# Power_MPU.net
KiCad netlist of a schematic drawn in Altium Designer
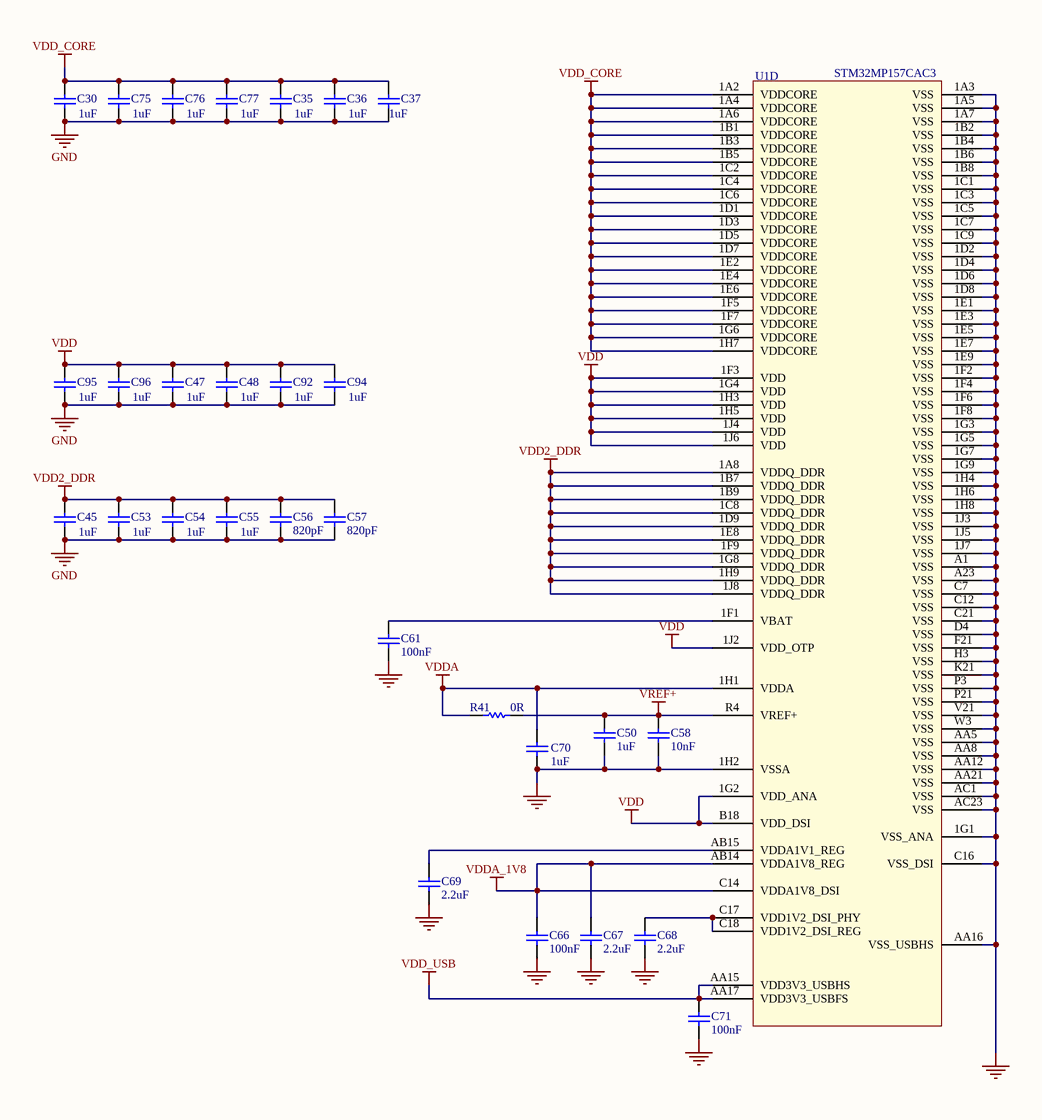
[diagram p0: Power_MPU.SchDoc]

(export (version "E")
  (design (tool "Eeschema 10.0.6"))
  (components
    (comp (ref "C30")
      (value "1uF")
      (footprint "C0402")
      (description "Capacitor, MLCC, 1uF, 25V, X5R, 10%, 0402, T=0,5mm")
      (fields
        (field (name "INTERNAL_PART_NUMBER") "MCD-00095")
        (field (name "MANUFACTURER_PART_NUMBER") "GRM155R61E105KA12")
        (field (name "PROVIDED_BY") "SUBCO")
      )
      (libsource (lib "MCD_PARTS_database") (part "Capacitor"))
    )
    (comp (ref "C35")
      (value "1uF")
      (footprint "C0402")
      (description "Capacitor, MLCC, 1uF, 25V, X5R, 10%, 0402, T=0,5mm")
      (fields
        (field (name "INTERNAL_PART_NUMBER") "MCD-00095")
        (field (name "MANUFACTURER_PART_NUMBER") "GRM155R61E105KA12")
        (field (name "PROVIDED_BY") "SUBCO")
      )
      (libsource (lib "MCD_PARTS_database") (part "Capacitor"))
    )
    (comp (ref "C36")
      (value "1uF")
      (footprint "C0402")
      (description "Capacitor, MLCC, 1uF, 25V, X5R, 10%, 0402, T=0,5mm")
      (fields
        (field (name "INTERNAL_PART_NUMBER") "MCD-00095")
        (field (name "MANUFACTURER_PART_NUMBER") "GRM155R61E105KA12")
        (field (name "PROVIDED_BY") "SUBCO")
      )
      (libsource (lib "MCD_PARTS_database") (part "Capacitor"))
    )
    (comp (ref "C37")
      (value "1uF")
      (footprint "C0402")
      (description "Capacitor, MLCC, 1uF, 25V, X5R, 10%, 0402, T=0,5mm")
      (fields
        (field (name "INTERNAL_PART_NUMBER") "MCD-00095")
        (field (name "MANUFACTURER_PART_NUMBER") "GRM155R61E105KA12")
        (field (name "PROVIDED_BY") "SUBCO")
      )
      (libsource (lib "MCD_PARTS_database") (part "Capacitor"))
    )
    (comp (ref "C45")
      (value "1uF")
      (footprint "C0402")
      (description "Capacitor, MLCC, 1uF, 25V, X5R, 10%, 0402, T=0,5mm")
      (fields
        (field (name "INTERNAL_PART_NUMBER") "MCD-00095")
        (field (name "MANUFACTURER_PART_NUMBER") "GRM155R61E105KA12")
        (field (name "PROVIDED_BY") "SUBCO")
      )
      (libsource (lib "MCD_PARTS_database") (part "Capacitor"))
    )
    (comp (ref "C47")
      (value "1uF")
      (footprint "C0402")
      (description "Capacitor, MLCC, 1uF, 25V, X5R, 10%, 0402, T=0,5mm")
      (fields
        (field (name "INTERNAL_PART_NUMBER") "MCD-00095")
        (field (name "MANUFACTURER_PART_NUMBER") "GRM155R61E105KA12")
        (field (name "PROVIDED_BY") "SUBCO")
      )
      (libsource (lib "MCD_PARTS_database") (part "Capacitor"))
    )
    (comp (ref "C48")
      (value "1uF")
      (footprint "C0402")
      (description "Capacitor, MLCC, 1uF, 25V, X5R, 10%, 0402, T=0,5mm")
      (fields
        (field (name "INTERNAL_PART_NUMBER") "MCD-00095")
        (field (name "MANUFACTURER_PART_NUMBER") "GRM155R61E105KA12")
        (field (name "PROVIDED_BY") "SUBCO")
      )
      (libsource (lib "MCD_PARTS_database") (part "Capacitor"))
    )
    (comp (ref "C50")
      (value "1uF")
      (footprint "C0402")
      (description "Capacitor, MLCC, 1uF, 25V, X5R, 10%, 0402, T=0,5mm")
      (fields
        (field (name "INTERNAL_PART_NUMBER") "MCD-00095")
        (field (name "MANUFACTURER_PART_NUMBER") "GRM155R61E105KA12")
        (field (name "PROVIDED_BY") "SUBCO")
      )
      (libsource (lib "MCD_PARTS_database") (part "Capacitor"))
    )
    (comp (ref "C53")
      (value "1uF")
      (footprint "C0402")
      (description "Capacitor, MLCC, 1uF, 25V, X5R, 10%, 0402, T=0,5mm")
      (fields
        (field (name "INTERNAL_PART_NUMBER") "MCD-00095")
        (field (name "MANUFACTURER_PART_NUMBER") "GRM155R61E105KA12")
        (field (name "PROVIDED_BY") "SUBCO")
      )
      (libsource (lib "MCD_PARTS_database") (part "Capacitor"))
    )
    (comp (ref "C54")
      (value "1uF")
      (footprint "C0402")
      (description "Capacitor, MLCC, 1uF, 25V, X5R, 10%, 0402, T=0,5mm")
      (fields
        (field (name "INTERNAL_PART_NUMBER") "MCD-00095")
        (field (name "MANUFACTURER_PART_NUMBER") "GRM155R61E105KA12")
        (field (name "PROVIDED_BY") "SUBCO")
      )
      (libsource (lib "MCD_PARTS_database") (part "Capacitor"))
    )
    (comp (ref "C55")
      (value "1uF")
      (footprint "C0402")
      (description "Capacitor, MLCC, 1uF, 25V, X5R, 10%, 0402, T=0,5mm")
      (fields
        (field (name "INTERNAL_PART_NUMBER") "MCD-00095")
        (field (name "MANUFACTURER_PART_NUMBER") "GRM155R61E105KA12")
        (field (name "PROVIDED_BY") "SUBCO")
      )
      (libsource (lib "MCD_PARTS_database") (part "Capacitor"))
    )
    (comp (ref "C56")
      (value "820pF")
      (footprint "C0402")
      (description "Capacitor, MLCC, 820pF, 50V, X7R, 10%, 0402, T=0.55mm")
      (fields
        (field (name "INTERNAL_PART_NUMBER") "MCD-01508")
        (field (name "MANUFACTURER_PART_NUMBER") "CC0402KRX7R9BB821")
        (field (name "PROVIDED_BY") "SUBCO")
      )
      (libsource (lib "MCD_PARTS_database") (part "Capacitor"))
    )
    (comp (ref "C57")
      (value "820pF")
      (footprint "C0402")
      (description "Capacitor, MLCC, 820pF, 50V, X7R, 10%, 0402, T=0.55mm")
      (fields
        (field (name "INTERNAL_PART_NUMBER") "MCD-01508")
        (field (name "MANUFACTURER_PART_NUMBER") "CC0402KRX7R9BB821")
        (field (name "PROVIDED_BY") "SUBCO")
      )
      (libsource (lib "MCD_PARTS_database") (part "Capacitor"))
    )
    (comp (ref "C58")
      (value "10nF")
      (footprint "C0402")
      (description "Capacitor, MLCC, 10nF, 16V, X7R, 10%, 0402, T=0.5mm")
      (fields
        (field (name "INTERNAL_PART_NUMBER") "MCD-00011")
        (field (name "MANUFACTURER_PART_NUMBER") "CC0402KRX7R7BB103")
        (field (name "PROVIDED_BY") "SUBCO")
      )
      (libsource (lib "MCD_PARTS_database") (part "Capacitor"))
    )
    (comp (ref "C61")
      (value "100nF")
      (footprint "C0402")
      (description "Capacitor, MLCC, 100nF, 16V, X7R, 10%, 0402, T=0.5mm")
      (fields
        (field (name "INTERNAL_PART_NUMBER") "MCD-00006")
        (field (name "MANUFACTURER_PART_NUMBER") "CC0402KRX7R7BB104")
        (field (name "PROVIDED_BY") "SUBCO")
      )
      (libsource (lib "MCD_PARTS_database") (part "Capacitor"))
    )
    (comp (ref "C66")
      (value "100nF")
      (footprint "C0402")
      (description "Capacitor, MLCC, 100nF, 16V, X7R, 10%, 0402, T=0.5mm")
      (fields
        (field (name "INTERNAL_PART_NUMBER") "MCD-00006")
        (field (name "MANUFACTURER_PART_NUMBER") "CC0402KRX7R7BB104")
        (field (name "PROVIDED_BY") "SUBCO")
      )
      (libsource (lib "MCD_PARTS_database") (part "Capacitor"))
    )
    (comp (ref "C67")
      (value "2.2uF")
      (footprint "C0402")
      (description "Capacitor,MLCC,2.2uF,6V3,X5R,10%,0402,T=0.5")
      (fields
        (field (name "INTERNAL_PART_NUMBER") "MCD-01823")
        (field (name "MANUFACTURER_PART_NUMBER") "GRM155R60J225KE95D")
        (field (name "PROVIDED_BY") "SUBCO")
      )
      (libsource (lib "MCD_PARTS_database") (part "Capacitor"))
    )
    (comp (ref "C68")
      (value "2.2uF")
      (footprint "C0402")
      (description "Capacitor,MLCC,2.2uF,6V3,X5R,10%,0402,T=0.5")
      (fields
        (field (name "INTERNAL_PART_NUMBER") "MCD-01823")
        (field (name "MANUFACTURER_PART_NUMBER") "GRM155R60J225KE95D")
        (field (name "PROVIDED_BY") "SUBCO")
      )
      (libsource (lib "MCD_PARTS_database") (part "Capacitor"))
    )
    (comp (ref "C69")
      (value "2.2uF")
      (footprint "C0402")
      (description "Capacitor,MLCC,2.2uF,6V3,X5R,10%,0402,T=0.5")
      (fields
        (field (name "INTERNAL_PART_NUMBER") "MCD-01823")
        (field (name "MANUFACTURER_PART_NUMBER") "GRM155R60J225KE95D")
        (field (name "PROVIDED_BY") "SUBCO")
      )
      (libsource (lib "MCD_PARTS_database") (part "Capacitor"))
    )
    (comp (ref "C70")
      (value "1uF")
      (footprint "C0402")
      (description "Capacitor, MLCC, 1uF, 25V, X5R, 10%, 0402, T=0,5mm")
      (fields
        (field (name "INTERNAL_PART_NUMBER") "MCD-00095")
        (field (name "MANUFACTURER_PART_NUMBER") "GRM155R61E105KA12")
        (field (name "PROVIDED_BY") "SUBCO")
      )
      (libsource (lib "MCD_PARTS_database") (part "Capacitor"))
    )
    (comp (ref "C71")
      (value "100nF")
      (footprint "C0402")
      (description "Capacitor, MLCC, 100nF, 16V, X7R, 10%, 0402, T=0.5mm")
      (fields
        (field (name "INTERNAL_PART_NUMBER") "MCD-00006")
        (field (name "MANUFACTURER_PART_NUMBER") "CC0402KRX7R7BB104")
        (field (name "PROVIDED_BY") "SUBCO")
      )
      (libsource (lib "MCD_PARTS_database") (part "Capacitor"))
    )
    (comp (ref "C75")
      (value "1uF")
      (footprint "C0402")
      (description "Capacitor, MLCC, 1uF, 25V, X5R, 10%, 0402, T=0,5mm")
      (fields
        (field (name "INTERNAL_PART_NUMBER") "MCD-00095")
        (field (name "MANUFACTURER_PART_NUMBER") "GRM155R61E105KA12")
        (field (name "PROVIDED_BY") "SUBCO")
      )
      (libsource (lib "MCD_PARTS_database") (part "Capacitor"))
    )
    (comp (ref "C76")
      (value "1uF")
      (footprint "C0402")
      (description "Capacitor, MLCC, 1uF, 25V, X5R, 10%, 0402, T=0,5mm")
      (fields
        (field (name "INTERNAL_PART_NUMBER") "MCD-00095")
        (field (name "MANUFACTURER_PART_NUMBER") "GRM155R61E105KA12")
        (field (name "PROVIDED_BY") "SUBCO")
      )
      (libsource (lib "MCD_PARTS_database") (part "Capacitor"))
    )
    (comp (ref "C77")
      (value "1uF")
      (footprint "C0402")
      (description "Capacitor, MLCC, 1uF, 25V, X5R, 10%, 0402, T=0,5mm")
      (fields
        (field (name "INTERNAL_PART_NUMBER") "MCD-00095")
        (field (name "MANUFACTURER_PART_NUMBER") "GRM155R61E105KA12")
        (field (name "PROVIDED_BY") "SUBCO")
      )
      (libsource (lib "MCD_PARTS_database") (part "Capacitor"))
    )
    (comp (ref "C92")
      (value "1uF")
      (footprint "C0402")
      (description "Capacitor, MLCC, 1uF, 25V, X5R, 10%, 0402, T=0,5mm")
      (fields
        (field (name "INTERNAL_PART_NUMBER") "MCD-00095")
        (field (name "MANUFACTURER_PART_NUMBER") "GRM155R61E105KA12")
        (field (name "PROVIDED_BY") "SUBCO")
      )
      (libsource (lib "MCD_PARTS_database") (part "Capacitor"))
    )
    (comp (ref "C94")
      (value "1uF")
      (footprint "C0402")
      (description "Capacitor, MLCC, 1uF, 25V, X5R, 10%, 0402, T=0,5mm")
      (fields
        (field (name "INTERNAL_PART_NUMBER") "MCD-00095")
        (field (name "MANUFACTURER_PART_NUMBER") "GRM155R61E105KA12")
        (field (name "PROVIDED_BY") "SUBCO")
      )
      (libsource (lib "MCD_PARTS_database") (part "Capacitor"))
    )
    (comp (ref "C95")
      (value "1uF")
      (footprint "C0402")
      (description "Capacitor, MLCC, 1uF, 25V, X5R, 10%, 0402, T=0,5mm")
      (fields
        (field (name "INTERNAL_PART_NUMBER") "MCD-00095")
        (field (name "MANUFACTURER_PART_NUMBER") "GRM155R61E105KA12")
        (field (name "PROVIDED_BY") "SUBCO")
      )
      (libsource (lib "MCD_PARTS_database") (part "Capacitor"))
    )
    (comp (ref "C96")
      (value "1uF")
      (footprint "C0402")
      (description "Capacitor, MLCC, 1uF, 25V, X5R, 10%, 0402, T=0,5mm")
      (fields
        (field (name "INTERNAL_PART_NUMBER") "MCD-00095")
        (field (name "MANUFACTURER_PART_NUMBER") "GRM155R61E105KA12")
        (field (name "PROVIDED_BY") "SUBCO")
      )
      (libsource (lib "MCD_PARTS_database") (part "Capacitor"))
    )
    (comp (ref "R41")
      (value "0R")
      (footprint "R0402")
      (description "Resistor,0R,0402,5%,1/16W")
      (fields
        (field (name "INTERNAL_PART_NUMBER") "MCD-00052")
        (field (name "MANUFACTURER_PART_NUMBER") "RC0402JR-070RL")
        (field (name "PROVIDED_BY") "SUBCO")
      )
      (libsource (lib "MCD_PARTS_database") (part "Resistor"))
    )
    (comp (ref "U1")
      (value "STM32MP157CAC3")
      (footprint "ICC_TFBGA361_12X12_STM32MP157CAC3_P050-065")
      (description "MPU TFBGA12x12 secure boot+crypto")
      (fields
        (field (name "INTERNAL_PART_NUMBER") "MCD-00677")
        (field (name "MANUFACTURER") "STMICROELECTRONICS")
        (field (name "PROVIDED_BY") "SUBCO with ST control")
      )
      (libsource (lib "MCD_PARTS_database") (part "STM32MP157CAC3"))
    )
  )
  (nets
    (net (code "1") (name "GND") (class "Default")
      (node (ref "C30") (pin "1") (pinfunction "1_1") (pintype "passive"))
      (node (ref "C35") (pin "1") (pinfunction "1_1") (pintype "passive"))
      (node (ref "C36") (pin "1") (pinfunction "1_1") (pintype "passive"))
      (node (ref "C37") (pin "1") (pinfunction "1_1") (pintype "passive"))
      (node (ref "C45") (pin "1") (pinfunction "1_1") (pintype "passive"))
      (node (ref "C47") (pin "1") (pinfunction "1_1") (pintype "passive"))
      (node (ref "C48") (pin "1") (pinfunction "1_1") (pintype "passive"))
      (node (ref "C50") (pin "1") (pinfunction "1_1") (pintype "passive"))
      (node (ref "C53") (pin "1") (pinfunction "1_1") (pintype "passive"))
      (node (ref "C54") (pin "1") (pinfunction "1_1") (pintype "passive"))
      (node (ref "C55") (pin "1") (pinfunction "1_1") (pintype "passive"))
      (node (ref "C56") (pin "1") (pinfunction "1_1") (pintype "passive"))
      (node (ref "C57") (pin "1") (pinfunction "1_1") (pintype "passive"))
      (node (ref "C58") (pin "1") (pinfunction "1_1") (pintype "passive"))
      (node (ref "C61") (pin "1") (pinfunction "1_1") (pintype "passive"))
      (node (ref "C66") (pin "1") (pinfunction "1_1") (pintype "passive"))
      (node (ref "C67") (pin "1") (pinfunction "1_1") (pintype "passive"))
      (node (ref "C68") (pin "1") (pinfunction "1_1") (pintype "passive"))
      (node (ref "C69") (pin "1") (pinfunction "1_1") (pintype "passive"))
      (node (ref "C70") (pin "1") (pinfunction "1_1") (pintype "passive"))
      (node (ref "C71") (pin "1") (pinfunction "1_1") (pintype "passive"))
      (node (ref "C75") (pin "1") (pinfunction "1_1") (pintype "passive"))
      (node (ref "C76") (pin "1") (pinfunction "1_1") (pintype "passive"))
      (node (ref "C77") (pin "1") (pinfunction "1_1") (pintype "passive"))
      (node (ref "C92") (pin "1") (pinfunction "1_1") (pintype "passive"))
      (node (ref "C94") (pin "1") (pinfunction "1_1") (pintype "passive"))
      (node (ref "C95") (pin "1") (pinfunction "1_1") (pintype "passive"))
      (node (ref "C96") (pin "1") (pinfunction "1_1") (pintype "passive"))
      (node (ref "U1") (pin "1A3") (pinfunction "VSS_1A3") (pintype "passive"))
      (node (ref "U1") (pin "1A5") (pinfunction "VSS_1A5") (pintype "passive"))
      (node (ref "U1") (pin "1A7") (pinfunction "VSS_1A7") (pintype "passive"))
      (node (ref "U1") (pin "1B2") (pinfunction "VSS_1B2") (pintype "passive"))
      (node (ref "U1") (pin "1B4") (pinfunction "VSS_1B4") (pintype "passive"))
      (node (ref "U1") (pin "1B6") (pinfunction "VSS_1B6") (pintype "passive"))
      (node (ref "U1") (pin "1B8") (pinfunction "VSS_1B8") (pintype "passive"))
      (node (ref "U1") (pin "1C1") (pinfunction "VSS_1C1") (pintype "passive"))
      (node (ref "U1") (pin "1C3") (pinfunction "VSS_1C3") (pintype "passive"))
      (node (ref "U1") (pin "1C5") (pinfunction "VSS_1C5") (pintype "passive"))
      (node (ref "U1") (pin "1C7") (pinfunction "VSS_1C7") (pintype "passive"))
      (node (ref "U1") (pin "1C9") (pinfunction "VSS_1C9") (pintype "passive"))
      (node (ref "U1") (pin "1D2") (pinfunction "VSS_1D2") (pintype "passive"))
      (node (ref "U1") (pin "1D4") (pinfunction "VSS_1D4") (pintype "passive"))
      (node (ref "U1") (pin "1D6") (pinfunction "VSS_1D6") (pintype "passive"))
      (node (ref "U1") (pin "1D8") (pinfunction "VSS_1D8") (pintype "passive"))
      (node (ref "U1") (pin "1E1") (pinfunction "VSS_1E1") (pintype "passive"))
      (node (ref "U1") (pin "1E3") (pinfunction "VSS_1E3") (pintype "passive"))
      (node (ref "U1") (pin "1E5") (pinfunction "VSS_1E5") (pintype "passive"))
      (node (ref "U1") (pin "1E7") (pinfunction "VSS_1E7") (pintype "passive"))
      (node (ref "U1") (pin "1E9") (pinfunction "VSS_1E9") (pintype "passive"))
      (node (ref "U1") (pin "1F2") (pinfunction "VSS_1F2") (pintype "passive"))
      (node (ref "U1") (pin "1F4") (pinfunction "VSS_1F4") (pintype "passive"))
      (node (ref "U1") (pin "1F6") (pinfunction "VSS_1F6") (pintype "passive"))
      (node (ref "U1") (pin "1F8") (pinfunction "VSS_1F8") (pintype "passive"))
      (node (ref "U1") (pin "1G1") (pinfunction "VSS_ANA_1G1") (pintype "passive"))
      (node (ref "U1") (pin "1G3") (pinfunction "VSS_1G3") (pintype "passive"))
      (node (ref "U1") (pin "1G5") (pinfunction "VSS_1G5") (pintype "passive"))
      (node (ref "U1") (pin "1G7") (pinfunction "VSS_1G7") (pintype "passive"))
      (node (ref "U1") (pin "1G9") (pinfunction "VSS_1G9") (pintype "passive"))
      (node (ref "U1") (pin "1H2") (pinfunction "VSSA_1H2") (pintype "passive"))
      (node (ref "U1") (pin "1H4") (pinfunction "VSS_1H4") (pintype "passive"))
      (node (ref "U1") (pin "1H6") (pinfunction "VSS_1H6") (pintype "passive"))
      (node (ref "U1") (pin "1H8") (pinfunction "VSS_1H8") (pintype "passive"))
      (node (ref "U1") (pin "1J3") (pinfunction "VSS_1J3") (pintype "passive"))
      (node (ref "U1") (pin "1J5") (pinfunction "VSS_1J5") (pintype "passive"))
      (node (ref "U1") (pin "1J7") (pinfunction "VSS_1J7") (pintype "passive"))
      (node (ref "U1") (pin "A1") (pinfunction "VSS_A1") (pintype "passive"))
      (node (ref "U1") (pin "A23") (pinfunction "VSS_A23") (pintype "passive"))
      (node (ref "U1") (pin "AA12") (pinfunction "VSS_AA12") (pintype "passive"))
      (node (ref "U1") (pin "AA16") (pinfunction "VSS_USBHS_AA16") (pintype "passive"))
      (node (ref "U1") (pin "AA21") (pinfunction "VSS_AA21") (pintype "passive"))
      (node (ref "U1") (pin "AA5") (pinfunction "VSS_AA5") (pintype "passive"))
      (node (ref "U1") (pin "AA8") (pinfunction "VSS_AA8") (pintype "passive"))
      (node (ref "U1") (pin "AC1") (pinfunction "VSS_AC1") (pintype "passive"))
      (node (ref "U1") (pin "AC23") (pinfunction "VSS_AC23") (pintype "passive"))
      (node (ref "U1") (pin "C12") (pinfunction "VSS_C12") (pintype "passive"))
      (node (ref "U1") (pin "C16") (pinfunction "VSS_DSI_C16") (pintype "passive"))
      (node (ref "U1") (pin "C21") (pinfunction "VSS_C21") (pintype "passive"))
      (node (ref "U1") (pin "C7") (pinfunction "VSS_C7") (pintype "passive"))
      (node (ref "U1") (pin "D4") (pinfunction "VSS_D4") (pintype "passive"))
      (node (ref "U1") (pin "F21") (pinfunction "VSS_F21") (pintype "passive"))
      (node (ref "U1") (pin "H3") (pinfunction "VSS_H3") (pintype "passive"))
      (node (ref "U1") (pin "K21") (pinfunction "VSS_K21") (pintype "passive"))
      (node (ref "U1") (pin "P21") (pinfunction "VSS_P21") (pintype "passive"))
      (node (ref "U1") (pin "P3") (pinfunction "VSS_P3") (pintype "passive"))
      (node (ref "U1") (pin "V21") (pinfunction "VSS_V21") (pintype "passive"))
      (node (ref "U1") (pin "W3") (pinfunction "VSS_W3") (pintype "passive"))
    )
    (net (code "2") (name "Net-(U1D-VBAT)") (class "Default")
      (node (ref "C61") (pin "2") (pinfunction "2_2") (pintype "passive"))
      (node (ref "U1") (pin "1F1") (pinfunction "VBAT_1F1") (pintype "passive"))
    )
    (net (code "3") (name "Net-(U1D-VDD1V2_DSI_PHY)") (class "Default")
      (node (ref "C68") (pin "2") (pinfunction "2_2") (pintype "passive"))
      (node (ref "U1") (pin "C17") (pinfunction "VDD1V2_DSI_PHY_C17") (pintype "passive"))
      (node (ref "U1") (pin "C18") (pinfunction "VDD1V2_DSI_REG_C18") (pintype "passive"))
    )
    (net (code "4") (name "Net-(U1D-VDDA1V1_REG)") (class "Default")
      (node (ref "C69") (pin "2") (pinfunction "2_2") (pintype "passive"))
      (node (ref "U1") (pin "AB15") (pinfunction "VDDA1V1_REG_AB15") (pintype "passive"))
    )
    (net (code "5") (name "VDD") (class "Default")
      (node (ref "C47") (pin "2") (pinfunction "2_2") (pintype "passive"))
      (node (ref "C48") (pin "2") (pinfunction "2_2") (pintype "passive"))
      (node (ref "C92") (pin "2") (pinfunction "2_2") (pintype "passive"))
      (node (ref "C94") (pin "2") (pinfunction "2_2") (pintype "passive"))
      (node (ref "C95") (pin "2") (pinfunction "2_2") (pintype "passive"))
      (node (ref "C96") (pin "2") (pinfunction "2_2") (pintype "passive"))
      (node (ref "U1") (pin "1F3") (pinfunction "VDD_1F3") (pintype "passive"))
      (node (ref "U1") (pin "1G2") (pinfunction "VDD_ANA_1G2") (pintype "passive"))
      (node (ref "U1") (pin "1G4") (pinfunction "VDD_1G4") (pintype "passive"))
      (node (ref "U1") (pin "1H3") (pinfunction "VDD_1H3") (pintype "passive"))
      (node (ref "U1") (pin "1H5") (pinfunction "VDD_1H5") (pintype "passive"))
      (node (ref "U1") (pin "1J2") (pinfunction "VDD_OTP_1J2") (pintype "passive"))
      (node (ref "U1") (pin "1J4") (pinfunction "VDD_1J4") (pintype "passive"))
      (node (ref "U1") (pin "1J6") (pinfunction "VDD_1J6") (pintype "passive"))
      (node (ref "U1") (pin "B18") (pinfunction "VDD_DSI_B18") (pintype "passive"))
    )
    (net (code "6") (name "VDD2_DDR") (class "Default")
      (node (ref "C45") (pin "2") (pinfunction "2_2") (pintype "passive"))
      (node (ref "C53") (pin "2") (pinfunction "2_2") (pintype "passive"))
      (node (ref "C54") (pin "2") (pinfunction "2_2") (pintype "passive"))
      (node (ref "C55") (pin "2") (pinfunction "2_2") (pintype "passive"))
      (node (ref "C56") (pin "2") (pinfunction "2_2") (pintype "passive"))
      (node (ref "C57") (pin "2") (pinfunction "2_2") (pintype "passive"))
      (node (ref "U1") (pin "1A8") (pinfunction "VDDQ_DDR_1A8") (pintype "passive"))
      (node (ref "U1") (pin "1B7") (pinfunction "VDDQ_DDR_1B7") (pintype "passive"))
      (node (ref "U1") (pin "1B9") (pinfunction "VDDQ_DDR_1B9") (pintype "passive"))
      (node (ref "U1") (pin "1C8") (pinfunction "VDDQ_DDR_1C8") (pintype "passive"))
      (node (ref "U1") (pin "1D9") (pinfunction "VDDQ_DDR_1D9") (pintype "passive"))
      (node (ref "U1") (pin "1E8") (pinfunction "VDDQ_DDR_1E8") (pintype "passive"))
      (node (ref "U1") (pin "1F9") (pinfunction "VDDQ_DDR_1F9") (pintype "passive"))
      (node (ref "U1") (pin "1G8") (pinfunction "VDDQ_DDR_1G8") (pintype "passive"))
      (node (ref "U1") (pin "1H9") (pinfunction "VDDQ_DDR_1H9") (pintype "passive"))
      (node (ref "U1") (pin "1J8") (pinfunction "VDDQ_DDR_1J8") (pintype "passive"))
    )
    (net (code "7") (name "VDDA") (class "Default")
      (node (ref "C70") (pin "2") (pinfunction "2_2") (pintype "passive"))
      (node (ref "R41") (pin "1") (pinfunction "1_1") (pintype "passive"))
      (node (ref "U1") (pin "1H1") (pinfunction "VDDA_1H1") (pintype "passive"))
    )
    (net (code "8") (name "VDDA_1V8") (class "Default")
      (node (ref "C66") (pin "2") (pinfunction "2_2") (pintype "passive"))
      (node (ref "C67") (pin "2") (pinfunction "2_2") (pintype "passive"))
      (node (ref "U1") (pin "AB14") (pinfunction "VDDA1V8_REG_AB14") (pintype "passive"))
      (node (ref "U1") (pin "C14") (pinfunction "VDDA1V8_DSI_C14") (pintype "passive"))
    )
    (net (code "9") (name "VDD_CORE") (class "Default")
      (node (ref "C30") (pin "2") (pinfunction "2_2") (pintype "passive"))
      (node (ref "C35") (pin "2") (pinfunction "2_2") (pintype "passive"))
      (node (ref "C36") (pin "2") (pinfunction "2_2") (pintype "passive"))
      (node (ref "C37") (pin "2") (pinfunction "2_2") (pintype "passive"))
      (node (ref "C75") (pin "2") (pinfunction "2_2") (pintype "passive"))
      (node (ref "C76") (pin "2") (pinfunction "2_2") (pintype "passive"))
      (node (ref "C77") (pin "2") (pinfunction "2_2") (pintype "passive"))
      (node (ref "U1") (pin "1A2") (pinfunction "VDDCORE_1A2") (pintype "passive"))
      (node (ref "U1") (pin "1A4") (pinfunction "VDDCORE_1A4") (pintype "passive"))
      (node (ref "U1") (pin "1A6") (pinfunction "VDDCORE_1A6") (pintype "passive"))
      (node (ref "U1") (pin "1B1") (pinfunction "VDDCORE_1B1") (pintype "passive"))
      (node (ref "U1") (pin "1B3") (pinfunction "VDDCORE_1B3") (pintype "passive"))
      (node (ref "U1") (pin "1B5") (pinfunction "VDDCORE_1B5") (pintype "passive"))
      (node (ref "U1") (pin "1C2") (pinfunction "VDDCORE_1C2") (pintype "passive"))
      (node (ref "U1") (pin "1C4") (pinfunction "VDDCORE_1C4") (pintype "passive"))
      (node (ref "U1") (pin "1C6") (pinfunction "VDDCORE_1C6") (pintype "passive"))
      (node (ref "U1") (pin "1D1") (pinfunction "VDDCORE_1D1") (pintype "passive"))
      (node (ref "U1") (pin "1D3") (pinfunction "VDDCORE_1D3") (pintype "passive"))
      (node (ref "U1") (pin "1D5") (pinfunction "VDDCORE_1D5") (pintype "passive"))
      (node (ref "U1") (pin "1D7") (pinfunction "VDDCORE_1D7") (pintype "passive"))
      (node (ref "U1") (pin "1E2") (pinfunction "VDDCORE_1E2") (pintype "passive"))
      (node (ref "U1") (pin "1E4") (pinfunction "VDDCORE_1E4") (pintype "passive"))
      (node (ref "U1") (pin "1E6") (pinfunction "VDDCORE_1E6") (pintype "passive"))
      (node (ref "U1") (pin "1F5") (pinfunction "VDDCORE_1F5") (pintype "passive"))
      (node (ref "U1") (pin "1F7") (pinfunction "VDDCORE_1F7") (pintype "passive"))
      (node (ref "U1") (pin "1G6") (pinfunction "VDDCORE_1G6") (pintype "passive"))
      (node (ref "U1") (pin "1H7") (pinfunction "VDDCORE_1H7") (pintype "passive"))
    )
    (net (code "10") (name "VDD_USB") (class "Default")
      (node (ref "C71") (pin "2") (pinfunction "2_2") (pintype "passive"))
      (node (ref "U1") (pin "AA15") (pinfunction "VDD3V3_USBHS_AA15") (pintype "passive"))
      (node (ref "U1") (pin "AA17") (pinfunction "VDD3V3_USBFS_AA17") (pintype "passive"))
    )
    (net (code "11") (name "VREF+") (class "Default")
      (node (ref "C50") (pin "2") (pinfunction "2_2") (pintype "passive"))
      (node (ref "C58") (pin "2") (pinfunction "2_2") (pintype "passive"))
      (node (ref "R41") (pin "2") (pinfunction "2_2") (pintype "passive"))
      (node (ref "U1") (pin "R4") (pinfunction "VREF+_R4") (pintype "passive"))
    )
  )
)
